# FED3_041319.net
KiCad netlist of a schematic drawn in EAGLE
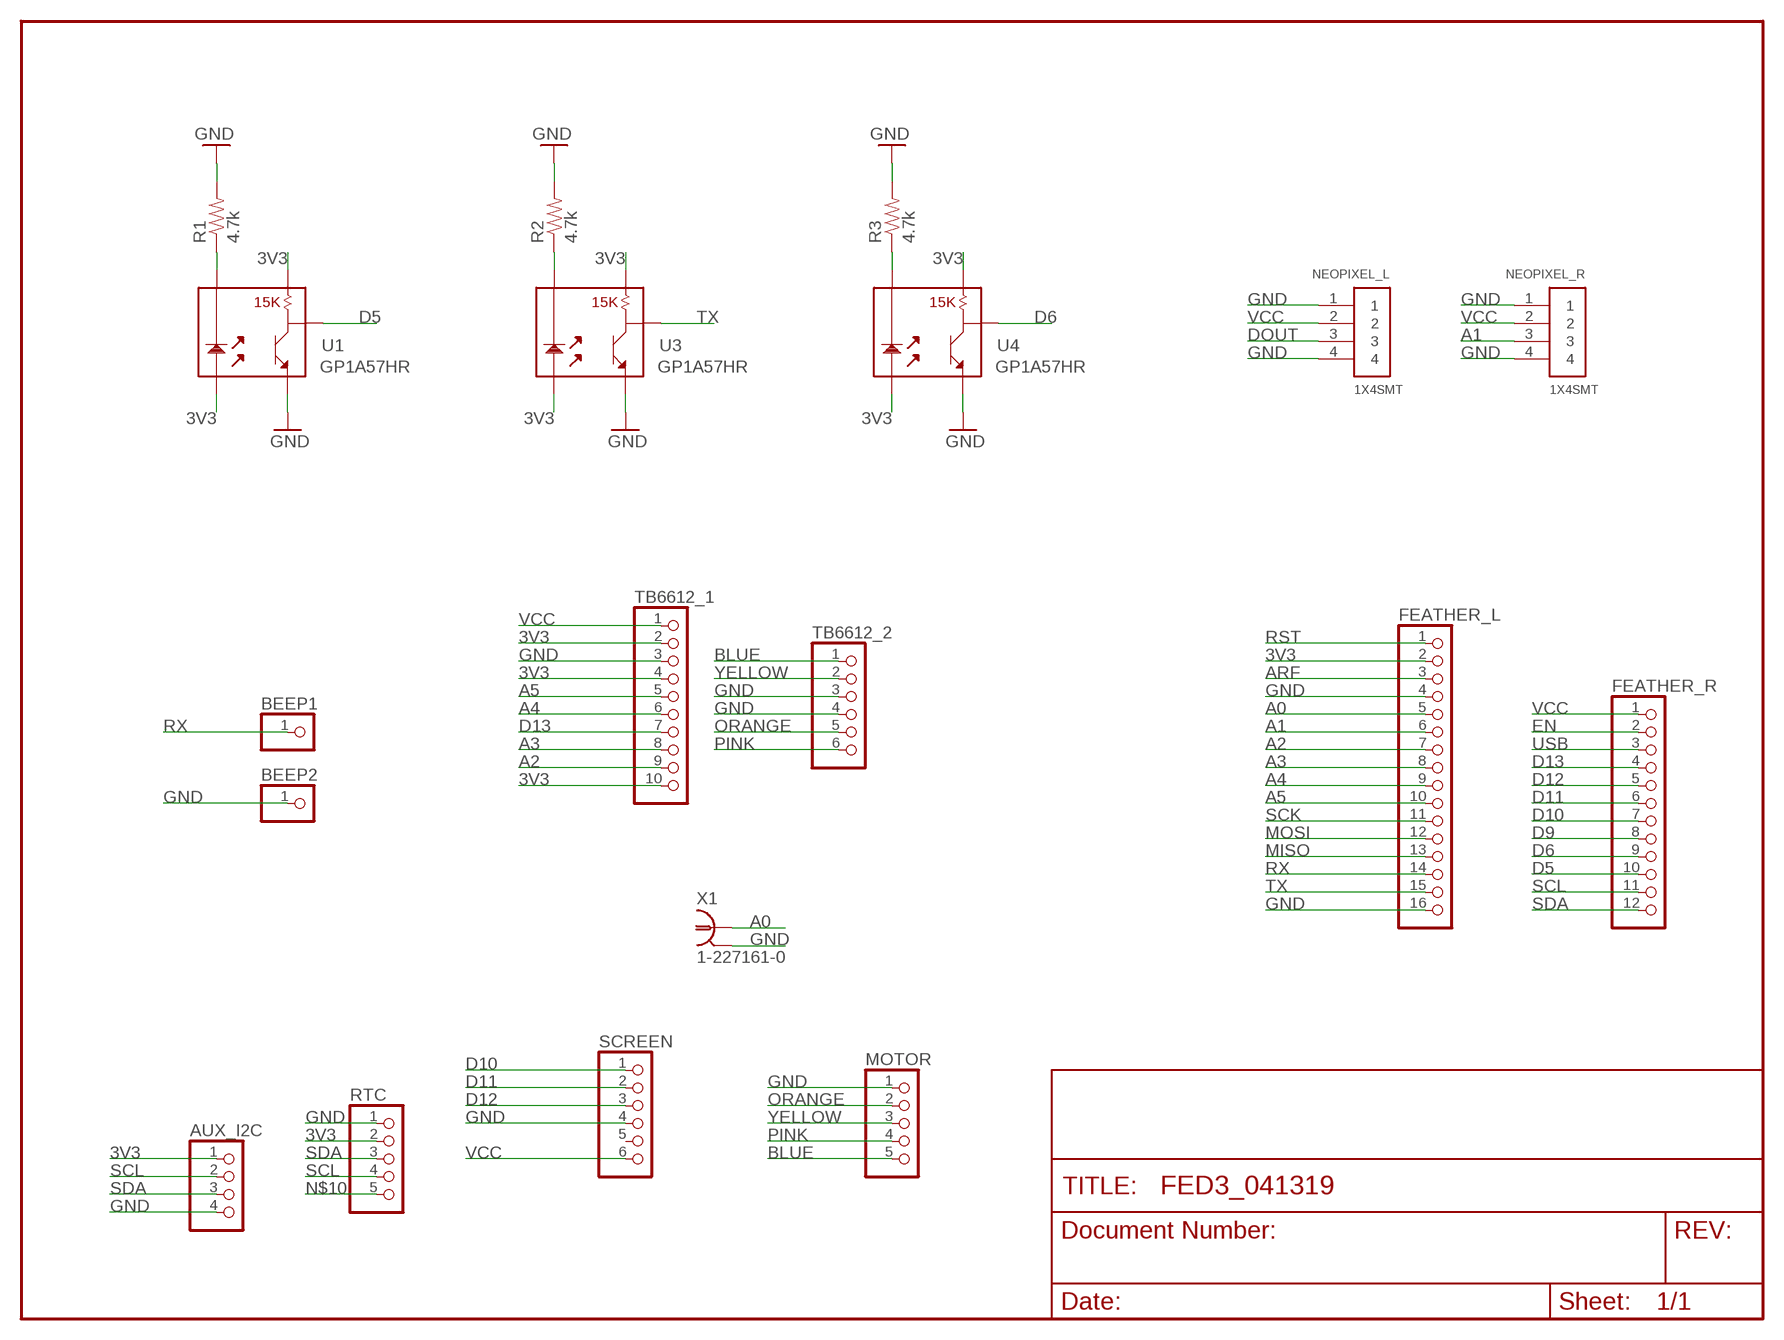
[diagram p0: schematic, sheet 1]

(export (version "E")
  (design (tool "Eeschema 10.0.6"))
  (components
    (comp (ref "AUX_I2C")
      (value "PINHD-1X4")
      (footprint "eagle-import:1X04")
      (libsource (lib "eagle-import") (part "PINHD-1X4"))
    )
    (comp (ref "BEEP1")
      (value "PINHD-1X1")
      (footprint "eagle-import:1X01")
      (libsource (lib "eagle-import") (part "PINHD-1X1"))
    )
    (comp (ref "BEEP2")
      (value "PINHD-1X1")
      (footprint "eagle-import:1X01")
      (libsource (lib "eagle-import") (part "PINHD-1X1"))
    )
    (comp (ref "FEATHER_L")
      (value "PINHD-1X16")
      (footprint "eagle-import:1X16")
      (libsource (lib "eagle-import") (part "PINHD-1X16"))
    )
    (comp (ref "FEATHER_R")
      (value "PINHD-1X12")
      (footprint "eagle-import:1X12")
      (libsource (lib "eagle-import") (part "PINHD-1X12"))
    )
    (comp (ref "MOTOR")
      (value "PINHD-1X5")
      (footprint "eagle-import:1X05")
      (libsource (lib "eagle-import") (part "PINHD-1X5"))
    )
    (comp (ref "NEOPIXEL_L")
      (value "1X4SMT")
      (footprint "eagle-import:1X4-SMT")
      (libsource (lib "eagle-import") (part "1X4SMT"))
    )
    (comp (ref "NEOPIXEL_R")
      (value "1X4SMT")
      (footprint "eagle-import:1X4-SMT")
      (libsource (lib "eagle-import") (part "1X4SMT"))
    )
    (comp (ref "R1")
      (value "4.7k")
      (footprint "eagle-import:AXIAL-0.3")
      (libsource (lib "eagle-import") (part "RESISTORPTH1"))
    )
    (comp (ref "R2")
      (value "4.7k")
      (footprint "eagle-import:AXIAL-0.3")
      (libsource (lib "eagle-import") (part "RESISTORPTH1"))
    )
    (comp (ref "R3")
      (value "4.7k")
      (footprint "eagle-import:AXIAL-0.3")
      (libsource (lib "eagle-import") (part "RESISTORPTH1"))
    )
    (comp (ref "RTC")
      (value "PINHD-1X5")
      (footprint "eagle-import:1X05")
      (libsource (lib "eagle-import") (part "PINHD-1X5"))
    )
    (comp (ref "SCREEN")
      (value "PINHD-1X6")
      (footprint "eagle-import:1X06")
      (libsource (lib "eagle-import") (part "PINHD-1X6"))
    )
    (comp (ref "TB6612_1")
      (value "PINHD-1X10")
      (footprint "eagle-import:1X10")
      (libsource (lib "eagle-import") (part "PINHD-1X10"))
    )
    (comp (ref "TB6612_2")
      (value "PINHD-1X6")
      (footprint "eagle-import:1X06")
      (libsource (lib "eagle-import") (part "PINHD-1X6"))
    )
    (comp (ref "U1")
      (value "GP1A57HR")
      (footprint "eagle-import:GP1A57HR")
      (libsource (lib "eagle-import") (part "GP1A57HR"))
    )
    (comp (ref "U3")
      (value "GP1A57HR")
      (footprint "eagle-import:GP1A57HR")
      (libsource (lib "eagle-import") (part "GP1A57HR"))
    )
    (comp (ref "U4")
      (value "GP1A57HR")
      (footprint "eagle-import:GP1A57HR")
      (libsource (lib "eagle-import") (part "GP1A57HR"))
    )
    (comp (ref "X1")
      (value "1-227161-0")
      (footprint "eagle-import:AMP_227161")
      (fields (field (name "MF") "TYCO ELECTRONICS") (field (name "MPN") "1-227161"))
      (libsource (lib "eagle-import") (part "?2271611--0"))
    )
  )
  (nets
    (net (code "1") (name "/3V3") (class "Default")
      (node (ref "AUX_I2C") (pin "1") (pinfunction "1_1") (pintype "passive"))
      (node (ref "FEATHER_L") (pin "2") (pinfunction "2_2") (pintype "passive"))
      (node (ref "RTC") (pin "2") (pinfunction "2_2") (pintype "passive"))
      (node (ref "TB6612_1") (pin "10") (pinfunction "10_10") (pintype "passive"))
      (node (ref "TB6612_1") (pin "2") (pinfunction "2_2") (pintype "passive"))
      (node (ref "TB6612_1") (pin "4") (pinfunction "4_4") (pintype "passive"))
      (node (ref "U1") (pin "1") (pinfunction "1_1") (pintype "bidirectional"))
      (node (ref "U1") (pin "3") (pinfunction "3_3") (pintype "bidirectional"))
      (node (ref "U3") (pin "1") (pinfunction "1_1") (pintype "bidirectional"))
      (node (ref "U3") (pin "3") (pinfunction "3_3") (pintype "bidirectional"))
      (node (ref "U4") (pin "1") (pinfunction "1_1") (pintype "bidirectional"))
      (node (ref "U4") (pin "3") (pinfunction "3_3") (pintype "bidirectional"))
    )
    (net (code "2") (name "/A0") (class "Default")
      (node (ref "FEATHER_L") (pin "5") (pinfunction "5_5") (pintype "passive"))
      (node (ref "X1") (pin "1") (pinfunction "1_1") (pintype "passive"))
    )
    (net (code "3") (name "/A1") (class "Default")
      (node (ref "FEATHER_L") (pin "6") (pinfunction "6_6") (pintype "passive"))
      (node (ref "NEOPIXEL_R") (pin "3") (pinfunction "3_3") (pintype "bidirectional"))
    )
    (net (code "4") (name "/A2") (class "Default")
      (node (ref "FEATHER_L") (pin "7") (pinfunction "7_7") (pintype "passive"))
      (node (ref "TB6612_1") (pin "9") (pinfunction "9_9") (pintype "passive"))
    )
    (net (code "5") (name "/A3") (class "Default")
      (node (ref "FEATHER_L") (pin "8") (pinfunction "8_8") (pintype "passive"))
      (node (ref "TB6612_1") (pin "8") (pinfunction "8_8") (pintype "passive"))
    )
    (net (code "6") (name "/A4") (class "Default")
      (node (ref "FEATHER_L") (pin "9") (pinfunction "9_9") (pintype "passive"))
      (node (ref "TB6612_1") (pin "6") (pinfunction "6_6") (pintype "passive"))
    )
    (net (code "7") (name "/A5") (class "Default")
      (node (ref "FEATHER_L") (pin "10") (pinfunction "10_10") (pintype "passive"))
      (node (ref "TB6612_1") (pin "5") (pinfunction "5_5") (pintype "passive"))
    )
    (net (code "8") (name "/ARF") (class "Default")
      (node (ref "FEATHER_L") (pin "3") (pinfunction "3_3") (pintype "passive"))
    )
    (net (code "9") (name "/BLUE") (class "Default")
      (node (ref "MOTOR") (pin "5") (pinfunction "5_5") (pintype "passive"))
      (node (ref "TB6612_2") (pin "1") (pinfunction "1_1") (pintype "passive"))
    )
    (net (code "10") (name "/D5") (class "Default")
      (node (ref "FEATHER_R") (pin "10") (pinfunction "10_10") (pintype "passive"))
      (node (ref "U1") (pin "4") (pinfunction "4_4") (pintype "bidirectional"))
    )
    (net (code "11") (name "/D6") (class "Default")
      (node (ref "FEATHER_R") (pin "9") (pinfunction "9_9") (pintype "passive"))
      (node (ref "U4") (pin "4") (pinfunction "4_4") (pintype "bidirectional"))
    )
    (net (code "12") (name "/D9") (class "Default")
      (node (ref "FEATHER_R") (pin "8") (pinfunction "8_8") (pintype "passive"))
    )
    (net (code "13") (name "/D10") (class "Default")
      (node (ref "FEATHER_R") (pin "7") (pinfunction "7_7") (pintype "passive"))
      (node (ref "SCREEN") (pin "1") (pinfunction "1_1") (pintype "passive"))
    )
    (net (code "14") (name "/D11") (class "Default")
      (node (ref "FEATHER_R") (pin "6") (pinfunction "6_6") (pintype "passive"))
      (node (ref "SCREEN") (pin "2") (pinfunction "2_2") (pintype "passive"))
    )
    (net (code "15") (name "/D12") (class "Default")
      (node (ref "FEATHER_R") (pin "5") (pinfunction "5_5") (pintype "passive"))
      (node (ref "SCREEN") (pin "3") (pinfunction "3_3") (pintype "passive"))
    )
    (net (code "16") (name "/D13") (class "Default")
      (node (ref "FEATHER_R") (pin "4") (pinfunction "4_4") (pintype "passive"))
      (node (ref "TB6612_1") (pin "7") (pinfunction "7_7") (pintype "passive"))
    )
    (net (code "17") (name "/DOUT") (class "Default")
      (node (ref "NEOPIXEL_L") (pin "3") (pinfunction "3_3") (pintype "bidirectional"))
    )
    (net (code "18") (name "/EN") (class "Default")
      (node (ref "FEATHER_R") (pin "2") (pinfunction "2_2") (pintype "passive"))
    )
    (net (code "19") (name "/MISO") (class "Default")
      (node (ref "FEATHER_L") (pin "13") (pinfunction "13_13") (pintype "passive"))
    )
    (net (code "20") (name "/MOSI") (class "Default")
      (node (ref "FEATHER_L") (pin "12") (pinfunction "12_12") (pintype "passive"))
    )
    (net (code "21") (name "/N$10") (class "Default")
      (node (ref "RTC") (pin "5") (pinfunction "5_5") (pintype "passive"))
    )
    (net (code "22") (name "/ORANGE") (class "Default")
      (node (ref "MOTOR") (pin "2") (pinfunction "2_2") (pintype "passive"))
      (node (ref "TB6612_2") (pin "5") (pinfunction "5_5") (pintype "passive"))
    )
    (net (code "23") (name "/PINK") (class "Default")
      (node (ref "MOTOR") (pin "4") (pinfunction "4_4") (pintype "passive"))
      (node (ref "TB6612_2") (pin "6") (pinfunction "6_6") (pintype "passive"))
    )
    (net (code "24") (name "/RST") (class "Default")
      (node (ref "FEATHER_L") (pin "1") (pinfunction "1_1") (pintype "passive"))
    )
    (net (code "25") (name "/RX") (class "Default")
      (node (ref "BEEP1") (pin "1") (pinfunction "1_1") (pintype "passive"))
      (node (ref "FEATHER_L") (pin "14") (pinfunction "14_14") (pintype "passive"))
    )
    (net (code "26") (name "/SCK") (class "Default")
      (node (ref "FEATHER_L") (pin "11") (pinfunction "11_11") (pintype "passive"))
    )
    (net (code "27") (name "/SCL") (class "Default")
      (node (ref "AUX_I2C") (pin "2") (pinfunction "2_2") (pintype "passive"))
      (node (ref "FEATHER_R") (pin "11") (pinfunction "11_11") (pintype "passive"))
      (node (ref "RTC") (pin "4") (pinfunction "4_4") (pintype "passive"))
    )
    (net (code "28") (name "/SDA") (class "Default")
      (node (ref "AUX_I2C") (pin "3") (pinfunction "3_3") (pintype "passive"))
      (node (ref "FEATHER_R") (pin "12") (pinfunction "12_12") (pintype "passive"))
      (node (ref "RTC") (pin "3") (pinfunction "3_3") (pintype "passive"))
    )
    (net (code "29") (name "/TX") (class "Default")
      (node (ref "FEATHER_L") (pin "15") (pinfunction "15_15") (pintype "passive"))
      (node (ref "U3") (pin "4") (pinfunction "4_4") (pintype "bidirectional"))
    )
    (net (code "30") (name "/USB") (class "Default")
      (node (ref "FEATHER_R") (pin "3") (pinfunction "3_3") (pintype "passive"))
    )
    (net (code "31") (name "/VCC") (class "Default")
      (node (ref "FEATHER_R") (pin "1") (pinfunction "1_1") (pintype "passive"))
      (node (ref "NEOPIXEL_L") (pin "2") (pinfunction "2_2") (pintype "bidirectional"))
      (node (ref "NEOPIXEL_R") (pin "2") (pinfunction "2_2") (pintype "bidirectional"))
      (node (ref "SCREEN") (pin "6") (pinfunction "6_6") (pintype "passive"))
      (node (ref "TB6612_1") (pin "1") (pinfunction "1_1") (pintype "passive"))
    )
    (net (code "32") (name "/YELLOW") (class "Default")
      (node (ref "MOTOR") (pin "3") (pinfunction "3_3") (pintype "passive"))
      (node (ref "TB6612_2") (pin "2") (pinfunction "2_2") (pintype "passive"))
    )
    (net (code "33") (name "GND") (class "Default")
      (node (ref "AUX_I2C") (pin "4") (pinfunction "4_4") (pintype "passive"))
      (node (ref "BEEP2") (pin "1") (pinfunction "1_1") (pintype "passive"))
      (node (ref "FEATHER_L") (pin "16") (pinfunction "16_16") (pintype "passive"))
      (node (ref "FEATHER_L") (pin "4") (pinfunction "4_4") (pintype "passive"))
      (node (ref "MOTOR") (pin "1") (pinfunction "1_1") (pintype "passive"))
      (node (ref "NEOPIXEL_L") (pin "1") (pinfunction "1_1") (pintype "bidirectional"))
      (node (ref "NEOPIXEL_L") (pin "4") (pinfunction "4_4") (pintype "bidirectional"))
      (node (ref "NEOPIXEL_R") (pin "1") (pinfunction "1_1") (pintype "bidirectional"))
      (node (ref "NEOPIXEL_R") (pin "4") (pinfunction "4_4") (pintype "bidirectional"))
      (node (ref "R1") (pin "P$2") (pinfunction "2_P$2") (pintype "passive"))
      (node (ref "R2") (pin "P$2") (pinfunction "2_P$2") (pintype "passive"))
      (node (ref "R3") (pin "P$2") (pinfunction "2_P$2") (pintype "passive"))
      (node (ref "RTC") (pin "1") (pinfunction "1_1") (pintype "passive"))
      (node (ref "SCREEN") (pin "4") (pinfunction "4_4") (pintype "passive"))
      (node (ref "TB6612_1") (pin "3") (pinfunction "3_3") (pintype "passive"))
      (node (ref "TB6612_2") (pin "3") (pinfunction "3_3") (pintype "passive"))
      (node (ref "TB6612_2") (pin "4") (pinfunction "4_4") (pintype "passive"))
      (node (ref "U1") (pin "5") (pinfunction "5_5") (pintype "bidirectional"))
      (node (ref "U3") (pin "5") (pinfunction "5_5") (pintype "bidirectional"))
      (node (ref "U4") (pin "5") (pinfunction "5_5") (pintype "bidirectional"))
      (node (ref "X1") (pin "2") (pinfunction "2_2") (pintype "passive"))
    )
    (net (code "34") (name "Net-(R1-1)") (class "Default")
      (node (ref "R1") (pin "P$1") (pinfunction "1_P$1") (pintype "passive"))
      (node (ref "U1") (pin "2") (pinfunction "2_2") (pintype "bidirectional"))
    )
    (net (code "35") (name "Net-(R2-1)") (class "Default")
      (node (ref "R2") (pin "P$1") (pinfunction "1_P$1") (pintype "passive"))
      (node (ref "U3") (pin "2") (pinfunction "2_2") (pintype "bidirectional"))
    )
    (net (code "36") (name "Net-(R3-1)") (class "Default")
      (node (ref "R3") (pin "P$1") (pinfunction "1_P$1") (pintype "passive"))
      (node (ref "U4") (pin "2") (pinfunction "2_2") (pintype "bidirectional"))
    )
    (net (code "37") (name "unconnected-(SCREEN-Pad5)") (class "Default")
      (node (ref "SCREEN") (pin "5") (pinfunction "5_5") (pintype "passive"))
    )
  )
)
